# USBSocket_Type10_v1_0.net
KiCad netlist of a schematic drawn in EAGLE
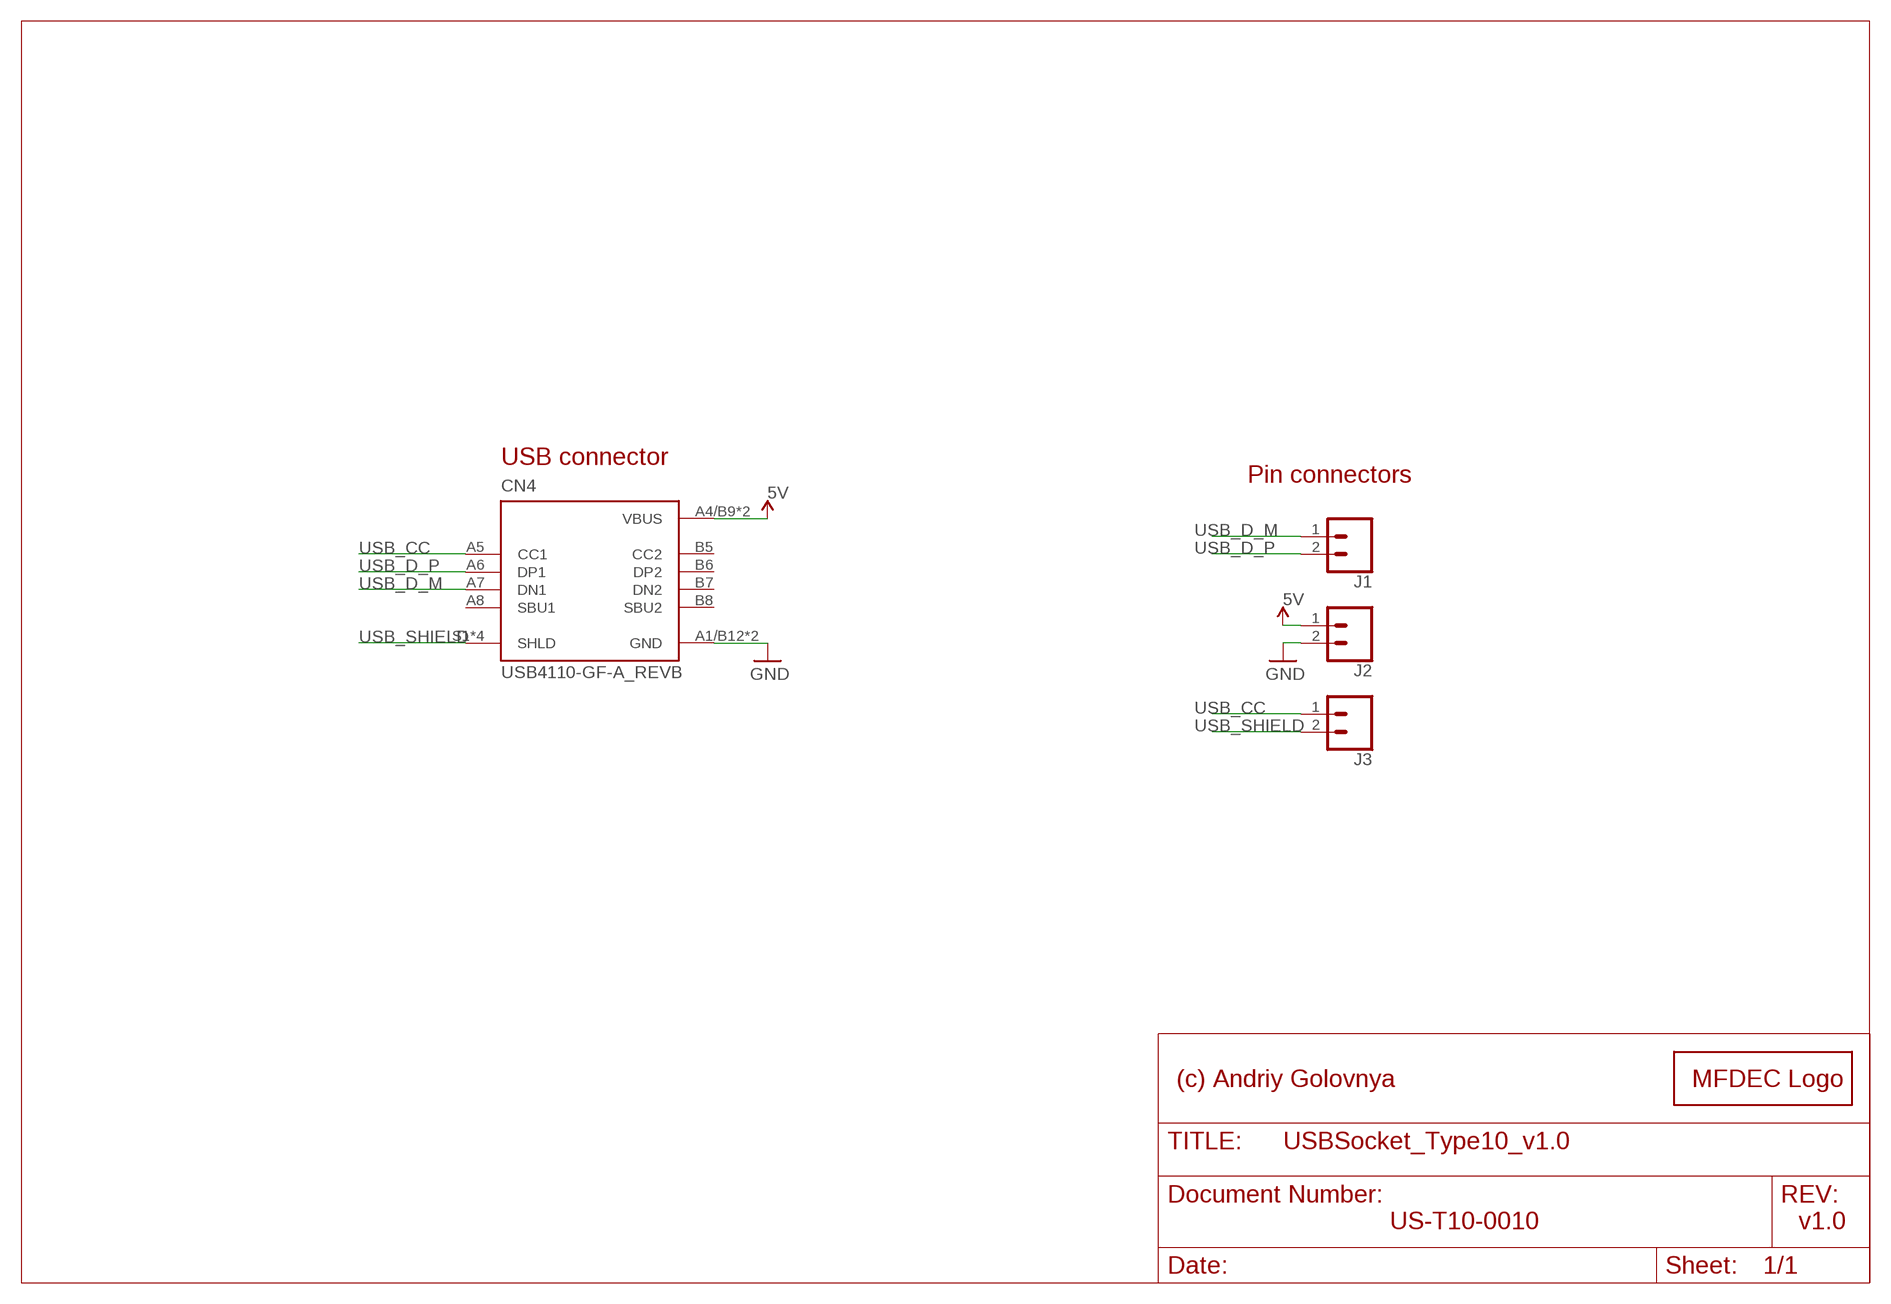
[diagram p0: schematic, sheet 1]

(export (version "E")
  (design (tool "Eeschema 10.0.6"))
  (components
    (comp (ref "CN4")
      (value "USB4110-GF-A_REVB")
      (footprint "eagle-import:GCT_USB4110-GF-A_REVB")
      (fields (field (name "MF") "GCT") (field (name "MP") "USB4110-GF-A"))
      (libsource (lib "eagle-import") (part "USB4110-GF-A_REVB"))
    )
    (comp (ref "J1")
      (value "CONN_02")
      (footprint "eagle-import:1X02")
      (libsource (lib "eagle-import") (part "CONN_02"))
    )
    (comp (ref "J2")
      (value "CONN_02")
      (footprint "eagle-import:1X02")
      (libsource (lib "eagle-import") (part "CONN_02"))
    )
    (comp (ref "J3")
      (value "CONN_02")
      (footprint "eagle-import:1X02")
      (libsource (lib "eagle-import") (part "CONN_02"))
    )
    (comp (ref "LOGO1")
      (value "MFDECLOGO_L_10MM")
      (footprint "eagle-import:MFDEC_L_10MM")
      (libsource (lib "eagle-import") (part "MFDECLOGO_L_10MM"))
    )
  )
  (nets
    (net (code "1") (name "/USB_CC") (class "Default")
      (node (ref "CN4") (pin "A5") (pinfunction "CC1_A5") (pintype "bidirectional"))
      (node (ref "J3") (pin "1") (pinfunction "1_1") (pintype "passive"))
    )
    (net (code "2") (name "/USB_D_M") (class "Default")
      (node (ref "CN4") (pin "A7") (pinfunction "DN1_A7") (pintype "bidirectional"))
      (node (ref "J1") (pin "1") (pinfunction "1_1") (pintype "passive"))
    )
    (net (code "3") (name "/USB_D_P") (class "Default")
      (node (ref "CN4") (pin "A6") (pinfunction "DP1_A6") (pintype "bidirectional"))
      (node (ref "J1") (pin "2") (pinfunction "2_2") (pintype "passive"))
    )
    (net (code "4") (name "/USB_SHIELD") (class "Default")
      (node (ref "CN4") (pin "S1") (pinfunction "SHLD_S1") (pintype "bidirectional"))
      (node (ref "CN4") (pin "S2") (pinfunction "SHLD_S2") (pintype "bidirectional"))
      (node (ref "CN4") (pin "S3") (pinfunction "SHLD_S3") (pintype "bidirectional"))
      (node (ref "CN4") (pin "S4") (pinfunction "SHLD_S4") (pintype "bidirectional"))
      (node (ref "J3") (pin "2") (pinfunction "2_2") (pintype "passive"))
    )
    (net (code "5") (name "5V") (class "Default")
      (node (ref "CN4") (pin "A4/B9") (pinfunction "VBUS_A4/B9") (pintype "power_in"))
      (node (ref "CN4") (pin "B4/A9") (pinfunction "VBUS_B4/A9") (pintype "power_in"))
      (node (ref "J2") (pin "1") (pinfunction "1_1") (pintype "passive"))
    )
    (net (code "6") (name "GND") (class "Default")
      (node (ref "CN4") (pin "A1/B12") (pinfunction "GND_A1/B12") (pintype "power_in"))
      (node (ref "CN4") (pin "B1/A12") (pinfunction "GND_B1/A12") (pintype "power_in"))
      (node (ref "J2") (pin "2") (pinfunction "2_2") (pintype "passive"))
    )
    (net (code "7") (name "unconnected-(CN4-CC2-PadB5)") (class "Default")
      (node (ref "CN4") (pin "B5") (pinfunction "CC2_B5") (pintype "bidirectional"))
    )
    (net (code "8") (name "unconnected-(CN4-DN2-PadB7)") (class "Default")
      (node (ref "CN4") (pin "B7") (pinfunction "DN2_B7") (pintype "bidirectional"))
    )
    (net (code "9") (name "unconnected-(CN4-DP2-PadB6)") (class "Default")
      (node (ref "CN4") (pin "B6") (pinfunction "DP2_B6") (pintype "bidirectional"))
    )
    (net (code "10") (name "unconnected-(CN4-SBU1-PadA8)") (class "Default")
      (node (ref "CN4") (pin "A8") (pinfunction "SBU1_A8") (pintype "bidirectional"))
    )
    (net (code "11") (name "unconnected-(CN4-SBU2-PadB8)") (class "Default")
      (node (ref "CN4") (pin "B8") (pinfunction "SBU2_B8") (pintype "bidirectional"))
    )
  )
)
